# adafruit_flora_mainboard.net
KiCad netlist of a schematic drawn in EAGLE
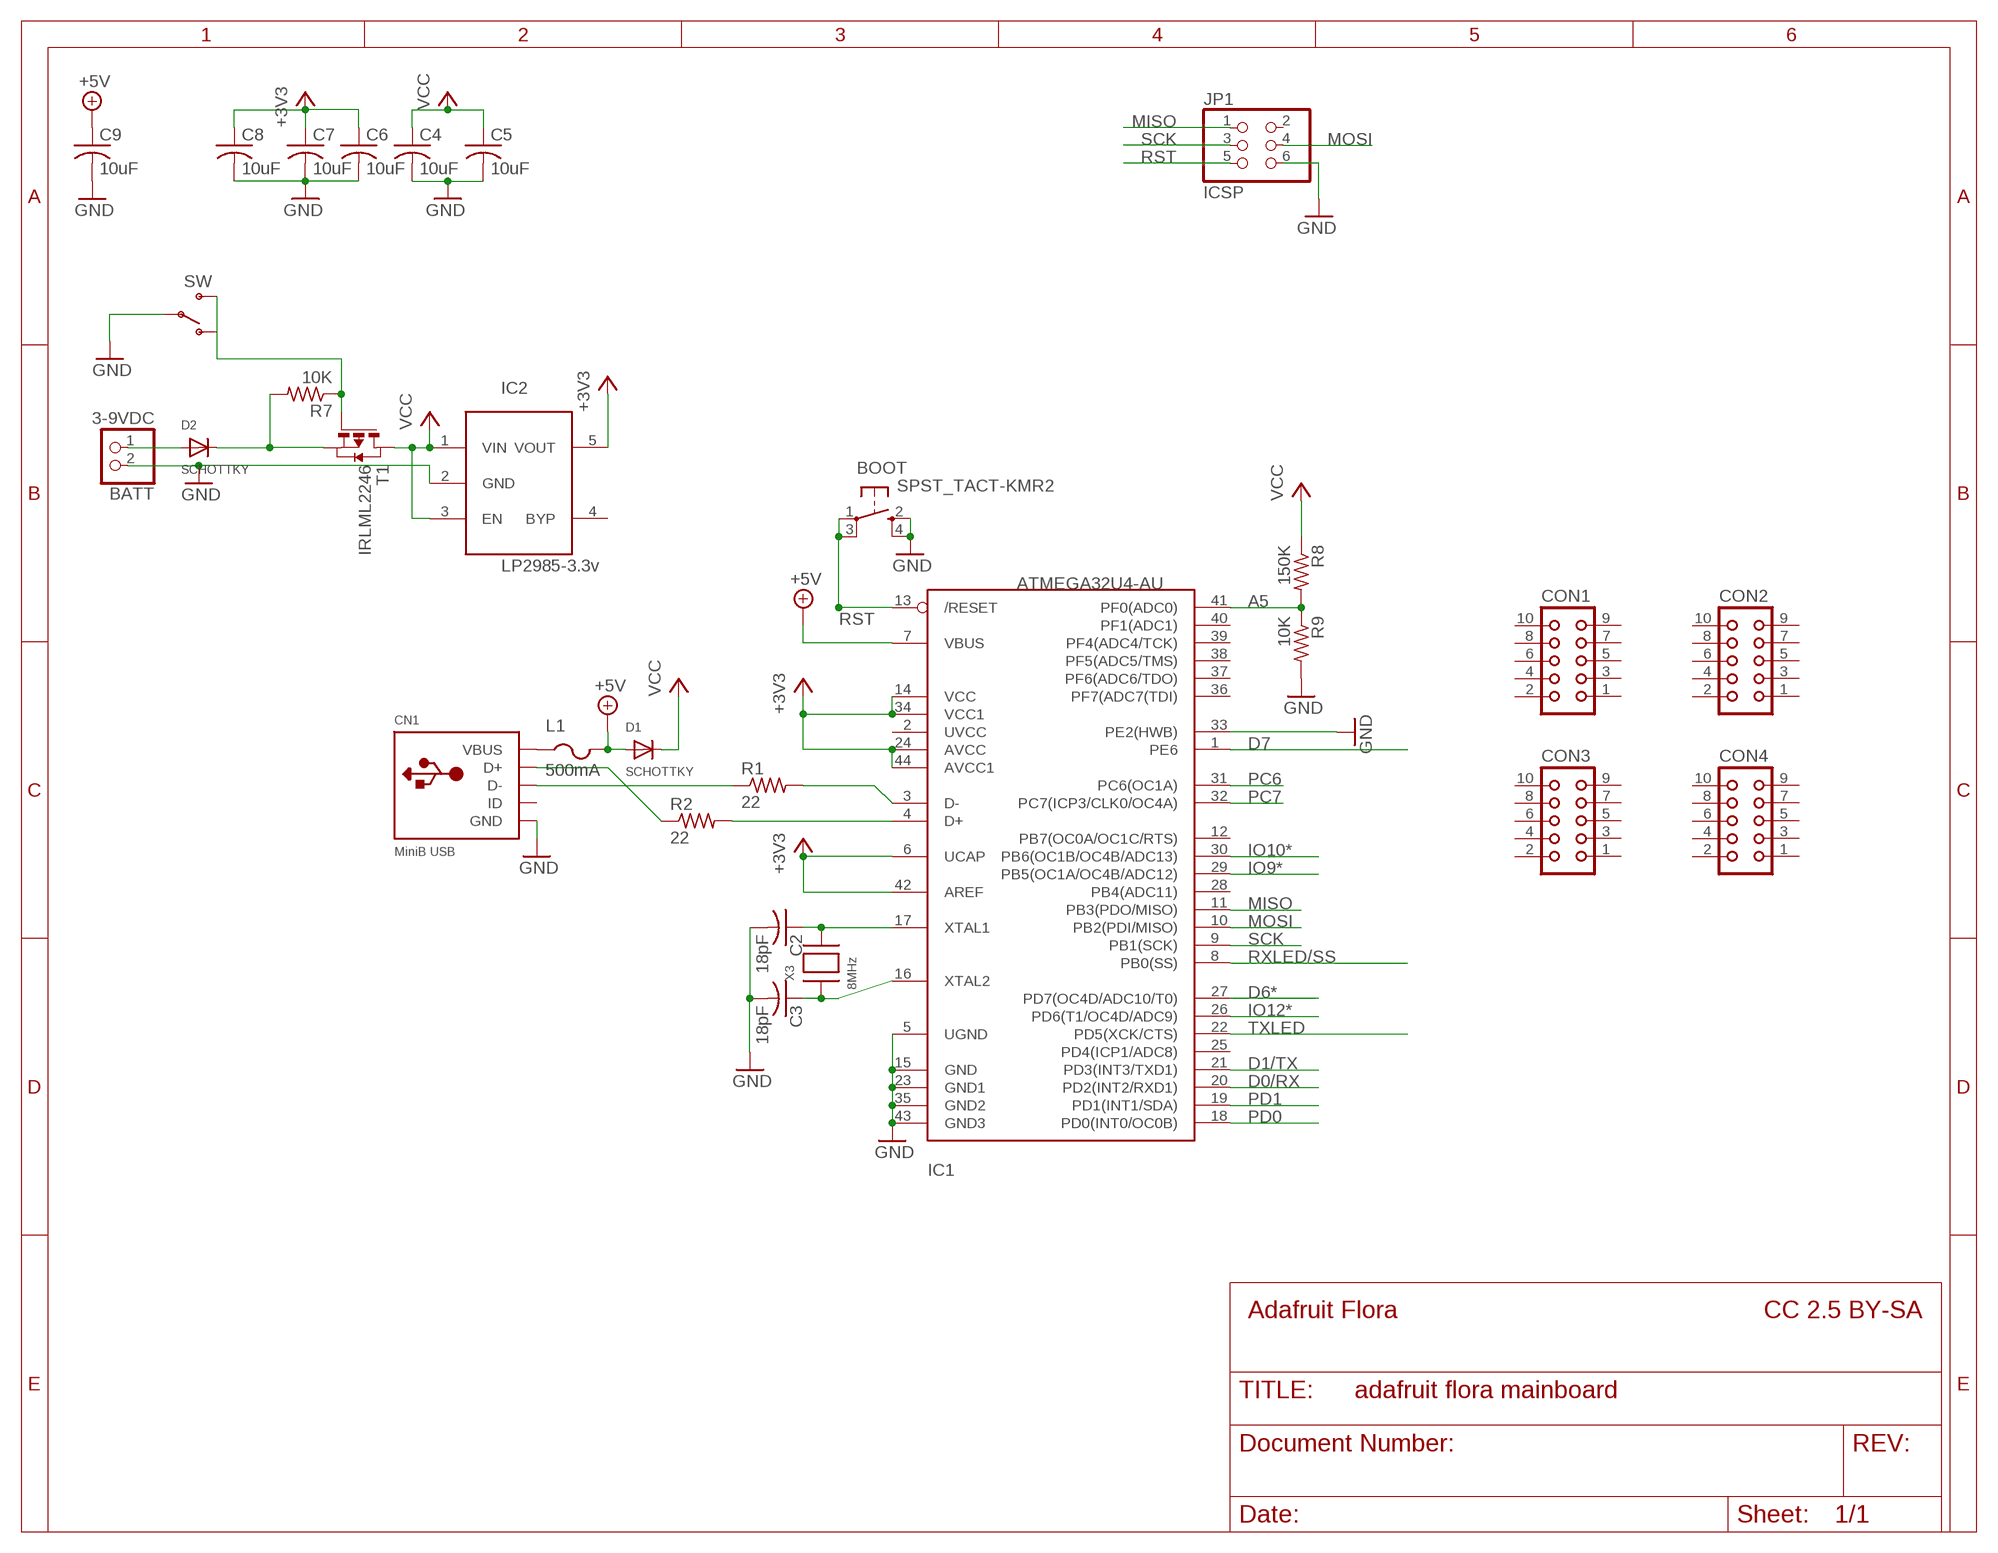
[diagram p0: schematic, sheet 1]

(export (version "E")
  (design (tool "Eeschema 10.0.6"))
  (components
    (comp (ref "BATT")
      (value "3-9VDC")
      (footprint "eagle-import:JST-PH-2-SMT-RA")
      (libsource (lib "eagle-import") (part "JST_2PIN-SMT-RA"))
    )
    (comp (ref "BOOT")
      (value "SPST_TACT-KMR2")
      (footprint "eagle-import:KMR2")
      (libsource (lib "eagle-import") (part "SPST_TACT-KMR2"))
    )
    (comp (ref "C2")
      (value "18pF")
      (footprint "eagle-import:C0805K")
      (libsource (lib "eagle-import") (part "C-USC0805K"))
    )
    (comp (ref "C3")
      (value "18pF")
      (footprint "eagle-import:C0805K")
      (libsource (lib "eagle-import") (part "C-USC0805K"))
    )
    (comp (ref "C4")
      (value "10uF")
      (footprint "eagle-import:C0805K")
      (libsource (lib "eagle-import") (part "C-USC0805K"))
    )
    (comp (ref "C5")
      (value "10uF")
      (footprint "eagle-import:C0805K")
      (libsource (lib "eagle-import") (part "C-USC0805K"))
    )
    (comp (ref "C6")
      (value "10uF")
      (footprint "eagle-import:C0805K")
      (libsource (lib "eagle-import") (part "C-USC0805K"))
    )
    (comp (ref "C7")
      (value "10uF")
      (footprint "eagle-import:C0805K")
      (libsource (lib "eagle-import") (part "C-USC0805K"))
    )
    (comp (ref "C8")
      (value "10uF")
      (footprint "eagle-import:C0805K")
      (libsource (lib "eagle-import") (part "C-USC0805K"))
    )
    (comp (ref "C9")
      (value "10uF")
      (footprint "eagle-import:C0805K")
      (libsource (lib "eagle-import") (part "C-USC0805K"))
    )
    (comp (ref "CN1")
      (value "MiniB USB")
      (footprint "eagle-import:USB-MINIB_LARGER")
      (libsource (lib "eagle-import") (part "USBMINIBLARGE"))
    )
    (comp (ref "CON1")
      (value "CON10")
      (footprint "eagle-import:CON10")
      (libsource (lib "eagle-import") (part "CON10"))
    )
    (comp (ref "CON2")
      (value "CON10")
      (footprint "eagle-import:CON10")
      (libsource (lib "eagle-import") (part "CON10"))
    )
    (comp (ref "CON3")
      (value "CON10")
      (footprint "eagle-import:CON10")
      (libsource (lib "eagle-import") (part "CON10"))
    )
    (comp (ref "CON4")
      (value "CON10")
      (footprint "eagle-import:CON10")
      (libsource (lib "eagle-import") (part "CON10"))
    )
    (comp (ref "D1")
      (value "SCHOTTKY")
      (footprint "eagle-import:SOD-123")
      (libsource (lib "eagle-import") (part "DIODESOD-123"))
    )
    (comp (ref "D2")
      (value "SCHOTTKY")
      (footprint "eagle-import:SOD-123")
      (libsource (lib "eagle-import") (part "DIODESOD-123"))
    )
    (comp (ref "IC1")
      (value "ATMEGA32U4-AU")
      (footprint "eagle-import:TQFP44")
      (libsource (lib "eagle-import") (part "ATMEGA32U4-AU"))
    )
    (comp (ref "IC2")
      (value "LP2985-3.3v")
      (footprint "eagle-import:SOT23-5L")
      (libsource (lib "eagle-import") (part "LP298XS"))
    )
    (comp (ref "JP1")
      (value "ICSP")
      (footprint "eagle-import:2X03")
      (libsource (lib "eagle-import") (part "PINHD-2X3"))
    )
    (comp (ref "L1")
      (value "500mA")
      (footprint "eagle-import:R1206")
      (libsource (lib "eagle-import") (part "PTCFUSE-1206"))
    )
    (comp (ref "R1")
      (value "22")
      (footprint "eagle-import:R0805")
      (libsource (lib "eagle-import") (part "R-US_R0805"))
    )
    (comp (ref "R2")
      (value "22")
      (footprint "eagle-import:R0805")
      (libsource (lib "eagle-import") (part "R-US_R0805"))
    )
    (comp (ref "R7")
      (value "10K")
      (footprint "eagle-import:R0805")
      (libsource (lib "eagle-import") (part "R-US_R0805"))
    )
    (comp (ref "R8")
      (value "150K")
      (footprint "eagle-import:R0805")
      (libsource (lib "eagle-import") (part "R-US_R0805"))
    )
    (comp (ref "R9")
      (value "10K")
      (footprint "eagle-import:R0805")
      (libsource (lib "eagle-import") (part "R-US_R0805"))
    )
    (comp (ref "SW")
      (value "SPDT")
      (footprint "eagle-import:SWITCH-SPDT-SMD")
      (libsource (lib "eagle-import") (part "SWITCH-SPSTSMD2"))
    )
    (comp (ref "T1")
      (value "IRLML2246")
      (footprint "eagle-import:SOT-23")
      (libsource (lib "eagle-import") (part "PMOSSOT23"))
    )
    (comp (ref "X3")
      (value "8MHz")
      (footprint "eagle-import:NX5032")
      (libsource (lib "eagle-import") (part "XTALNX5032"))
    )
  )
  (nets
    (net (code "1") (name "+3V3") (class "Default")
      (node (ref "C6") (pin "1") (pinfunction "1_1") (pintype "passive"))
      (node (ref "C7") (pin "1") (pinfunction "1_1") (pintype "passive"))
      (node (ref "C8") (pin "1") (pinfunction "1_1") (pintype "passive"))
      (node (ref "IC1") (pin "14") (pinfunction "VCC_14") (pintype "bidirectional"))
      (node (ref "IC1") (pin "24") (pinfunction "AVCC_24") (pintype "bidirectional"))
      (node (ref "IC1") (pin "34") (pinfunction "VCC1_34") (pintype "bidirectional"))
      (node (ref "IC1") (pin "42") (pinfunction "AREF_42") (pintype "bidirectional"))
      (node (ref "IC1") (pin "44") (pinfunction "AVCC1_44") (pintype "bidirectional"))
      (node (ref "IC1") (pin "6") (pinfunction "UCAP_6") (pintype "bidirectional"))
      (node (ref "IC2") (pin "5") (pinfunction "VOUT_5") (pintype "bidirectional"))
    )
    (net (code "2") (name "+5V") (class "Default")
      (node (ref "C9") (pin "1") (pinfunction "1_1") (pintype "passive"))
      (node (ref "D1") (pin "A") (pinfunction "A_A") (pintype "passive"))
      (node (ref "IC1") (pin "7") (pinfunction "VBUS_7") (pintype "bidirectional"))
      (node (ref "L1") (pin "2") (pinfunction "2_2") (pintype "passive"))
    )
    (net (code "3") (name "/A5") (class "Default")
      (node (ref "IC1") (pin "41") (pinfunction "PF0(ADC0)_41") (pintype "bidirectional"))
      (node (ref "R8") (pin "2") (pinfunction "2_2") (pintype "passive"))
      (node (ref "R9") (pin "1") (pinfunction "1_1") (pintype "passive"))
    )
    (net (code "4") (name "/D0{slash}RX") (class "Default")
      (node (ref "IC1") (pin "20") (pinfunction "PD2(INT2/RXD1)_20") (pintype "bidirectional"))
    )
    (net (code "5") (name "/D1{slash}TX") (class "Default")
      (node (ref "IC1") (pin "21") (pinfunction "PD3(INT3/TXD1)_21") (pintype "bidirectional"))
    )
    (net (code "6") (name "/D6*") (class "Default")
      (node (ref "IC1") (pin "27") (pinfunction "PD7(OC4D/ADC10/T0)_27") (pintype "bidirectional"))
    )
    (net (code "7") (name "/D7") (class "Default")
      (node (ref "IC1") (pin "1") (pinfunction "PE6_1") (pintype "bidirectional"))
    )
    (net (code "8") (name "/IO9*") (class "Default")
      (node (ref "IC1") (pin "29") (pinfunction "PB5(OC1A/OC4B/ADC12)_29") (pintype "bidirectional"))
    )
    (net (code "9") (name "/IO10*") (class "Default")
      (node (ref "IC1") (pin "30") (pinfunction "PB6(OC1B/OC4B/ADC13)_30") (pintype "bidirectional"))
    )
    (net (code "10") (name "/IO12*") (class "Default")
      (node (ref "IC1") (pin "26") (pinfunction "PD6(T1/OC4D/ADC9)_26") (pintype "bidirectional"))
    )
    (net (code "11") (name "/MISO") (class "Default")
      (node (ref "IC1") (pin "11") (pinfunction "PB3(PDO/MISO)_11") (pintype "bidirectional"))
      (node (ref "JP1") (pin "1") (pinfunction "1_1") (pintype "passive"))
    )
    (net (code "12") (name "/MOSI") (class "Default")
      (node (ref "IC1") (pin "10") (pinfunction "PB2(PDI/MISO)_10") (pintype "bidirectional"))
      (node (ref "JP1") (pin "4") (pinfunction "4_4") (pintype "passive"))
    )
    (net (code "13") (name "/PC6") (class "Default")
      (node (ref "IC1") (pin "31") (pinfunction "PC6(OC1A)_31") (pintype "bidirectional"))
    )
    (net (code "14") (name "/PC7") (class "Default")
      (node (ref "IC1") (pin "32") (pinfunction "PC7(ICP3/CLK0/OC4A)_32") (pintype "bidirectional"))
    )
    (net (code "15") (name "/PD0") (class "Default")
      (node (ref "IC1") (pin "18") (pinfunction "PD0(INT0/OC0B)_18") (pintype "bidirectional"))
    )
    (net (code "16") (name "/PD1") (class "Default")
      (node (ref "IC1") (pin "19") (pinfunction "PD1(INT1/SDA)_19") (pintype "bidirectional"))
    )
    (net (code "17") (name "/RST") (class "Default")
      (node (ref "BOOT") (pin "1") (pinfunction "P_1") (pintype "passive"))
      (node (ref "BOOT") (pin "3") (pinfunction "P1_3") (pintype "passive"))
      (node (ref "IC1") (pin "13") (pinfunction "/RESET_13") (pintype "bidirectional"))
      (node (ref "JP1") (pin "5") (pinfunction "5_5") (pintype "passive"))
    )
    (net (code "18") (name "/RXLED{slash}SS") (class "Default")
      (node (ref "IC1") (pin "8") (pinfunction "PB0(SS)_8") (pintype "bidirectional"))
    )
    (net (code "19") (name "/SCK") (class "Default")
      (node (ref "IC1") (pin "9") (pinfunction "PB1(SCK)_9") (pintype "bidirectional"))
      (node (ref "JP1") (pin "3") (pinfunction "3_3") (pintype "passive"))
    )
    (net (code "20") (name "/TXLED") (class "Default")
      (node (ref "IC1") (pin "22") (pinfunction "PD5(XCK/CTS)_22") (pintype "bidirectional"))
    )
    (net (code "21") (name "GND") (class "Default")
      (node (ref "BATT") (pin "2") (pinfunction "1_2") (pintype "passive"))
      (node (ref "BOOT") (pin "2") (pinfunction "S_2") (pintype "passive"))
      (node (ref "BOOT") (pin "4") (pinfunction "S1_4") (pintype "passive"))
      (node (ref "C2") (pin "2") (pinfunction "2_2") (pintype "passive"))
      (node (ref "C3") (pin "2") (pinfunction "2_2") (pintype "passive"))
      (node (ref "C4") (pin "2") (pinfunction "2_2") (pintype "passive"))
      (node (ref "C5") (pin "2") (pinfunction "2_2") (pintype "passive"))
      (node (ref "C6") (pin "2") (pinfunction "2_2") (pintype "passive"))
      (node (ref "C7") (pin "2") (pinfunction "2_2") (pintype "passive"))
      (node (ref "C8") (pin "2") (pinfunction "2_2") (pintype "passive"))
      (node (ref "C9") (pin "2") (pinfunction "2_2") (pintype "passive"))
      (node (ref "CN1") (pin "GND") (pinfunction "GND_GND") (pintype "power_in"))
      (node (ref "IC1") (pin "15") (pinfunction "GND_15") (pintype "bidirectional"))
      (node (ref "IC1") (pin "23") (pinfunction "GND1_23") (pintype "bidirectional"))
      (node (ref "IC1") (pin "33") (pinfunction "PE2(HWB)_33") (pintype "bidirectional"))
      (node (ref "IC1") (pin "35") (pinfunction "GND2_35") (pintype "bidirectional"))
      (node (ref "IC1") (pin "43") (pinfunction "GND3_43") (pintype "bidirectional"))
      (node (ref "IC1") (pin "5") (pinfunction "UGND_5") (pintype "bidirectional"))
      (node (ref "IC2") (pin "2") (pinfunction "GND_2") (pintype "bidirectional"))
      (node (ref "JP1") (pin "6") (pinfunction "6_6") (pintype "passive"))
      (node (ref "R9") (pin "2") (pinfunction "2_2") (pintype "passive"))
      (node (ref "SW") (pin "2") (pinfunction "P_2") (pintype "passive"))
    )
    (net (code "22") (name "Net-(BATT-2)") (class "Default")
      (node (ref "BATT") (pin "1") (pinfunction "2_1") (pintype "passive"))
      (node (ref "D2") (pin "A") (pinfunction "A_A") (pintype "passive"))
    )
    (net (code "23") (name "Net-(CN1-PadD+)") (class "Default")
      (node (ref "CN1") (pin "D+") (pinfunction "D+_D+") (pintype "bidirectional"))
      (node (ref "R2") (pin "1") (pinfunction "1_1") (pintype "passive"))
    )
    (net (code "24") (name "Net-(CN1-PadD-)") (class "Default")
      (node (ref "CN1") (pin "D-") (pinfunction "D-_D-") (pintype "bidirectional"))
      (node (ref "R1") (pin "1") (pinfunction "1_1") (pintype "passive"))
    )
    (net (code "25") (name "Net-(CN1-PadVBUS)") (class "Default")
      (node (ref "CN1") (pin "VBUS") (pinfunction "VBUS_VBUS") (pintype "power_in"))
      (node (ref "L1") (pin "1") (pinfunction "1_1") (pintype "passive"))
    )
    (net (code "26") (name "Net-(IC1-D+)") (class "Default")
      (node (ref "IC1") (pin "4") (pinfunction "D+_4") (pintype "bidirectional"))
      (node (ref "R2") (pin "2") (pinfunction "2_2") (pintype "passive"))
    )
    (net (code "27") (name "Net-(IC1-D-)") (class "Default")
      (node (ref "IC1") (pin "3") (pinfunction "D-_3") (pintype "bidirectional"))
      (node (ref "R1") (pin "2") (pinfunction "2_2") (pintype "passive"))
    )
    (net (code "28") (name "Net-(IC1-XTAL1)") (class "Default")
      (node (ref "C2") (pin "1") (pinfunction "1_1") (pintype "passive"))
      (node (ref "IC1") (pin "17") (pinfunction "XTAL1_17") (pintype "bidirectional"))
      (node (ref "X3") (pin "P$2") (pinfunction "P$2_P$2") (pintype "bidirectional"))
    )
    (net (code "29") (name "Net-(IC1-XTAL2)") (class "Default")
      (node (ref "C3") (pin "1") (pinfunction "1_1") (pintype "passive"))
      (node (ref "IC1") (pin "16") (pinfunction "XTAL2_16") (pintype "bidirectional"))
      (node (ref "X3") (pin "P$1") (pinfunction "P$1_P$1") (pintype "bidirectional"))
    )
    (net (code "30") (name "Net-(SW-S)") (class "Default")
      (node (ref "R7") (pin "1") (pinfunction "1_1") (pintype "passive"))
      (node (ref "SW") (pin "3") (pinfunction "S_3") (pintype "passive"))
      (node (ref "T1") (pin "3") (pinfunction "G_3") (pintype "passive"))
    )
    (net (code "31") (name "Net-(T1-S)") (class "Default")
      (node (ref "D2") (pin "C") (pinfunction "C_C") (pintype "passive"))
      (node (ref "R7") (pin "2") (pinfunction "2_2") (pintype "passive"))
      (node (ref "T1") (pin "2") (pinfunction "S_2") (pintype "passive"))
    )
    (net (code "32") (name "VCC") (class "Default")
      (node (ref "C4") (pin "1") (pinfunction "1_1") (pintype "passive"))
      (node (ref "C5") (pin "1") (pinfunction "1_1") (pintype "passive"))
      (node (ref "D1") (pin "C") (pinfunction "C_C") (pintype "passive"))
      (node (ref "IC2") (pin "1") (pinfunction "VIN_1") (pintype "bidirectional"))
      (node (ref "IC2") (pin "3") (pinfunction "EN_3") (pintype "bidirectional"))
      (node (ref "R8") (pin "1") (pinfunction "1_1") (pintype "passive"))
      (node (ref "T1") (pin "1") (pinfunction "D_1") (pintype "passive"))
    )
    (net (code "33") (name "unconnected-(CN1-PadID)") (class "Default")
      (node (ref "CN1") (pin "ID") (pinfunction "ID_ID") (pintype "bidirectional"))
    )
    (net (code "34") (name "unconnected-(CON1-Pad1)") (class "Default")
      (node (ref "CON1") (pin "1") (pinfunction "1_1") (pintype "passive"))
    )
    (net (code "35") (name "unconnected-(CON1-Pad2)") (class "Default")
      (node (ref "CON1") (pin "2") (pinfunction "2_2") (pintype "passive"))
    )
    (net (code "36") (name "unconnected-(CON1-Pad3)") (class "Default")
      (node (ref "CON1") (pin "3") (pinfunction "3_3") (pintype "passive"))
    )
    (net (code "37") (name "unconnected-(CON1-Pad4)") (class "Default")
      (node (ref "CON1") (pin "4") (pinfunction "4_4") (pintype "passive"))
    )
    (net (code "38") (name "unconnected-(CON1-Pad5)") (class "Default")
      (node (ref "CON1") (pin "5") (pinfunction "5_5") (pintype "passive"))
    )
    (net (code "39") (name "unconnected-(CON1-Pad6)") (class "Default")
      (node (ref "CON1") (pin "6") (pinfunction "6_6") (pintype "passive"))
    )
    (net (code "40") (name "unconnected-(CON1-Pad7)") (class "Default")
      (node (ref "CON1") (pin "7") (pinfunction "7_7") (pintype "passive"))
    )
    (net (code "41") (name "unconnected-(CON1-Pad8)") (class "Default")
      (node (ref "CON1") (pin "8") (pinfunction "8_8") (pintype "passive"))
    )
    (net (code "42") (name "unconnected-(CON1-Pad9)") (class "Default")
      (node (ref "CON1") (pin "9") (pinfunction "9_9") (pintype "passive"))
    )
    (net (code "43") (name "unconnected-(CON1-Pad10)") (class "Default")
      (node (ref "CON1") (pin "10") (pinfunction "10_10") (pintype "passive"))
    )
    (net (code "44") (name "unconnected-(CON2-Pad1)") (class "Default")
      (node (ref "CON2") (pin "1") (pinfunction "1_1") (pintype "passive"))
    )
    (net (code "45") (name "unconnected-(CON2-Pad2)") (class "Default")
      (node (ref "CON2") (pin "2") (pinfunction "2_2") (pintype "passive"))
    )
    (net (code "46") (name "unconnected-(CON2-Pad3)") (class "Default")
      (node (ref "CON2") (pin "3") (pinfunction "3_3") (pintype "passive"))
    )
    (net (code "47") (name "unconnected-(CON2-Pad4)") (class "Default")
      (node (ref "CON2") (pin "4") (pinfunction "4_4") (pintype "passive"))
    )
    (net (code "48") (name "unconnected-(CON2-Pad5)") (class "Default")
      (node (ref "CON2") (pin "5") (pinfunction "5_5") (pintype "passive"))
    )
    (net (code "49") (name "unconnected-(CON2-Pad6)") (class "Default")
      (node (ref "CON2") (pin "6") (pinfunction "6_6") (pintype "passive"))
    )
    (net (code "50") (name "unconnected-(CON2-Pad7)") (class "Default")
      (node (ref "CON2") (pin "7") (pinfunction "7_7") (pintype "passive"))
    )
    (net (code "51") (name "unconnected-(CON2-Pad8)") (class "Default")
      (node (ref "CON2") (pin "8") (pinfunction "8_8") (pintype "passive"))
    )
    (net (code "52") (name "unconnected-(CON2-Pad9)") (class "Default")
      (node (ref "CON2") (pin "9") (pinfunction "9_9") (pintype "passive"))
    )
    (net (code "53") (name "unconnected-(CON2-Pad10)") (class "Default")
      (node (ref "CON2") (pin "10") (pinfunction "10_10") (pintype "passive"))
    )
    (net (code "54") (name "unconnected-(CON3-Pad1)") (class "Default")
      (node (ref "CON3") (pin "1") (pinfunction "1_1") (pintype "passive"))
    )
    (net (code "55") (name "unconnected-(CON3-Pad2)") (class "Default")
      (node (ref "CON3") (pin "2") (pinfunction "2_2") (pintype "passive"))
    )
    (net (code "56") (name "unconnected-(CON3-Pad3)") (class "Default")
      (node (ref "CON3") (pin "3") (pinfunction "3_3") (pintype "passive"))
    )
    (net (code "57") (name "unconnected-(CON3-Pad4)") (class "Default")
      (node (ref "CON3") (pin "4") (pinfunction "4_4") (pintype "passive"))
    )
    (net (code "58") (name "unconnected-(CON3-Pad5)") (class "Default")
      (node (ref "CON3") (pin "5") (pinfunction "5_5") (pintype "passive"))
    )
    (net (code "59") (name "unconnected-(CON3-Pad6)") (class "Default")
      (node (ref "CON3") (pin "6") (pinfunction "6_6") (pintype "passive"))
    )
    (net (code "60") (name "unconnected-(CON3-Pad7)") (class "Default")
      (node (ref "CON3") (pin "7") (pinfunction "7_7") (pintype "passive"))
    )
    (net (code "61") (name "unconnected-(CON3-Pad8)") (class "Default")
      (node (ref "CON3") (pin "8") (pinfunction "8_8") (pintype "passive"))
    )
    (net (code "62") (name "unconnected-(CON3-Pad9)") (class "Default")
      (node (ref "CON3") (pin "9") (pinfunction "9_9") (pintype "passive"))
    )
    (net (code "63") (name "unconnected-(CON3-Pad10)") (class "Default")
      (node (ref "CON3") (pin "10") (pinfunction "10_10") (pintype "passive"))
    )
    (net (code "64") (name "unconnected-(CON4-Pad1)") (class "Default")
      (node (ref "CON4") (pin "1") (pinfunction "1_1") (pintype "passive"))
    )
    (net (code "65") (name "unconnected-(CON4-Pad2)") (class "Default")
      (node (ref "CON4") (pin "2") (pinfunction "2_2") (pintype "passive"))
    )
    (net (code "66") (name "unconnected-(CON4-Pad3)") (class "Default")
      (node (ref "CON4") (pin "3") (pinfunction "3_3") (pintype "passive"))
    )
    (net (code "67") (name "unconnected-(CON4-Pad4)") (class "Default")
      (node (ref "CON4") (pin "4") (pinfunction "4_4") (pintype "passive"))
    )
    (net (code "68") (name "unconnected-(CON4-Pad5)") (class "Default")
      (node (ref "CON4") (pin "5") (pinfunction "5_5") (pintype "passive"))
    )
    (net (code "69") (name "unconnected-(CON4-Pad6)") (class "Default")
      (node (ref "CON4") (pin "6") (pinfunction "6_6") (pintype "passive"))
    )
    (net (code "70") (name "unconnected-(CON4-Pad7)") (class "Default")
      (node (ref "CON4") (pin "7") (pinfunction "7_7") (pintype "passive"))
    )
    (net (code "71") (name "unconnected-(CON4-Pad8)") (class "Default")
      (node (ref "CON4") (pin "8") (pinfunction "8_8") (pintype "passive"))
    )
    (net (code "72") (name "unconnected-(CON4-Pad9)") (class "Default")
      (node (ref "CON4") (pin "9") (pinfunction "9_9") (pintype "passive"))
    )
    (net (code "73") (name "unconnected-(CON4-Pad10)") (class "Default")
      (node (ref "CON4") (pin "10") (pinfunction "10_10") (pintype "passive"))
    )
    (net (code "74") (name "unconnected-(IC1-PB4(ADC11)-Pad28)") (class "Default")
      (node (ref "IC1") (pin "28") (pinfunction "PB4(ADC11)_28") (pintype "bidirectional"))
    )
    (net (code "75") (name "unconnected-(IC1-PB7(OC0A{slash}OC1C{slash}RTS)-Pad12)") (class "Default")
      (node (ref "IC1") (pin "12") (pinfunction "PB7(OC0A/OC1C/RTS)_12") (pintype "bidirectional"))
    )
    (net (code "76") (name "unconnected-(IC1-PD4(ICP1{slash}ADC8)-Pad25)") (class "Default")
      (node (ref "IC1") (pin "25") (pinfunction "PD4(ICP1/ADC8)_25") (pintype "bidirectional"))
    )
    (net (code "77") (name "unconnected-(IC1-PF1(ADC1)-Pad40)") (class "Default")
      (node (ref "IC1") (pin "40") (pinfunction "PF1(ADC1)_40") (pintype "bidirectional"))
    )
    (net (code "78") (name "unconnected-(IC1-PF4(ADC4{slash}TCK)-Pad39)") (class "Default")
      (node (ref "IC1") (pin "39") (pinfunction "PF4(ADC4/TCK)_39") (pintype "bidirectional"))
    )
    (net (code "79") (name "unconnected-(IC1-PF5(ADC5{slash}TMS)-Pad38)") (class "Default")
      (node (ref "IC1") (pin "38") (pinfunction "PF5(ADC5/TMS)_38") (pintype "bidirectional"))
    )
    (net (code "80") (name "unconnected-(IC1-PF6(ADC6{slash}TDO)-Pad37)") (class "Default")
      (node (ref "IC1") (pin "37") (pinfunction "PF6(ADC6/TDO)_37") (pintype "bidirectional"))
    )
    (net (code "81") (name "unconnected-(IC1-PF7(ADC7(TDI)-Pad36)") (class "Default")
      (node (ref "IC1") (pin "36") (pinfunction "PF7(ADC7(TDI)_36") (pintype "bidirectional"))
    )
    (net (code "82") (name "unconnected-(IC1-UVCC-Pad2)") (class "Default")
      (node (ref "IC1") (pin "2") (pinfunction "UVCC_2") (pintype "bidirectional"))
    )
    (net (code "83") (name "unconnected-(IC2-BYP-Pad4)") (class "Default")
      (node (ref "IC2") (pin "4") (pinfunction "BYP_4") (pintype "bidirectional"))
    )
    (net (code "84") (name "unconnected-(JP1-Pad2)") (class "Default")
      (node (ref "JP1") (pin "2") (pinfunction "2_2") (pintype "passive"))
    )
    (net (code "85") (name "unconnected-(SW-O-Pad1)") (class "Default")
      (node (ref "SW") (pin "1") (pinfunction "O_1") (pintype "passive"))
    )
  )
)
